# on_shore.net
KiCad netlist of a schematic drawn in EAGLE
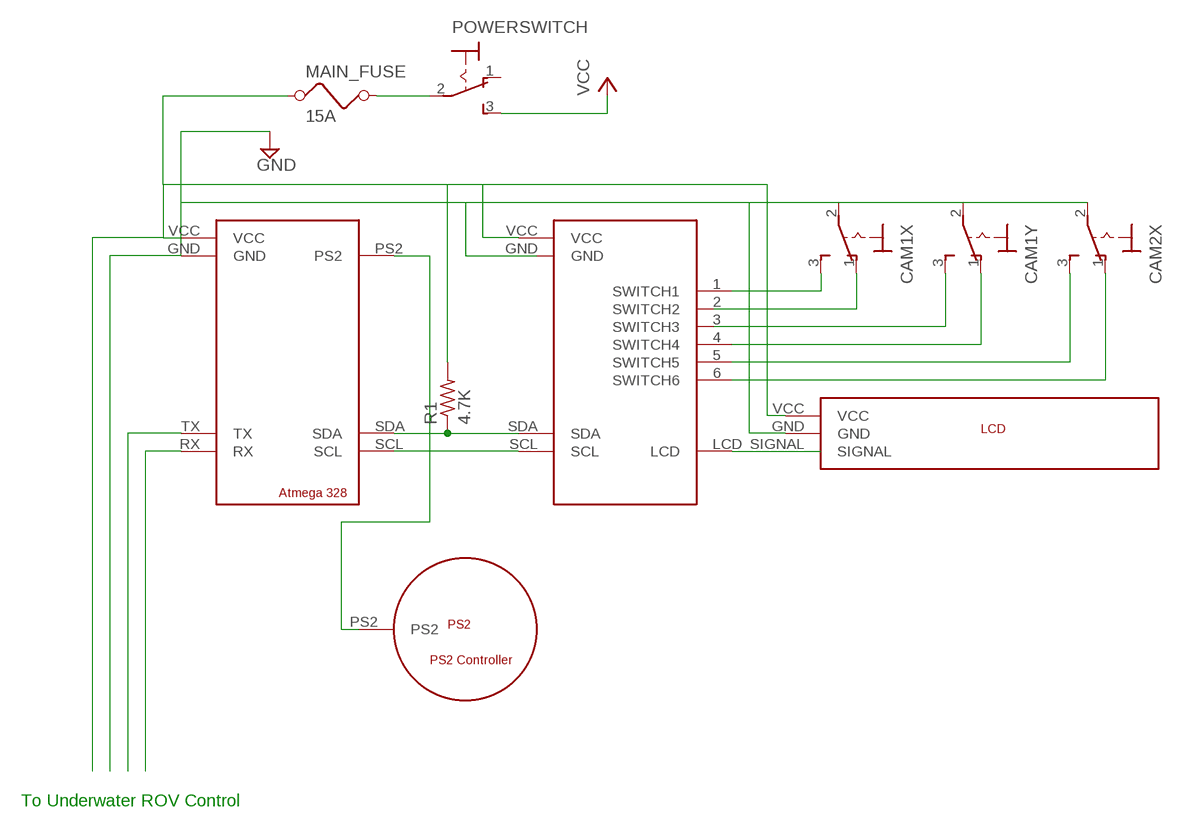
[diagram p0: schematic, sheet 1]

(export (version "E")
  (design (tool "Eeschema 10.0.6"))
  (components
    (comp (ref "CAM1X")
      (value "320-916")
      (footprint "eagle-import:320-916")
      (libsource (lib "eagle-import") (part "320-916"))
    )
    (comp (ref "CAM1Y")
      (value "320-916")
      (footprint "eagle-import:320-916")
      (libsource (lib "eagle-import") (part "320-916"))
    )
    (comp (ref "CAM2X")
      (value "320-916")
      (footprint "eagle-import:320-916")
      (libsource (lib "eagle-import") (part "320-916"))
    )
    (comp (ref "MAIN_FUSE")
      (value "15A")
      (footprint "eagle-import:FUSE")
      (libsource (lib "eagle-import") (part "FUSE"))
    )
    (comp (ref "POWERSWITCH")
      (value "320-916")
      (footprint "eagle-import:320-916")
      (libsource (lib "eagle-import") (part "320-916"))
    )
    (comp (ref "R1")
      (value "4.7K")
      (footprint "eagle-import:0204_7")
      (libsource (lib "eagle-import") (part "R-US_0204/7"))
    )
    (comp (ref "U$1")
      (value "CONTROL")
      (footprint "eagle-import:CONTROL")
      (libsource (lib "eagle-import") (part "CONTROL"))
    )
    (comp (ref "U$2")
      (value "AUX")
      (footprint "eagle-import:AUX")
      (libsource (lib "eagle-import") (part "AUX"))
    )
    (comp (ref "U$3")
      (value "LCD")
      (footprint "eagle-import:LCD")
      (libsource (lib "eagle-import") (part "LCD"))
    )
    (comp (ref "U$4")
      (value "PS2")
      (footprint "eagle-import:PS2")
      (libsource (lib "eagle-import") (part "PS2"))
    )
  )
  (nets
    (net (code "1") (name "GND") (class "Default")
      (node (ref "CAM2X") (pin "2") (pinfunction "P_2") (pintype "passive"))
      (node (ref "U$1") (pin "GND") (pinfunction "GND_GND") (pintype "bidirectional"))
      (node (ref "U$3") (pin "GND") (pinfunction "GND_GND") (pintype "bidirectional"))
    )
    (net (code "2") (name "Net-(CAM1X-S)") (class "Default")
      (node (ref "CAM1X") (pin "3") (pinfunction "S_3") (pintype "passive"))
      (node (ref "U$2") (pin "1") (pinfunction "SWITCH1_1") (pintype "bidirectional"))
    )
    (net (code "3") (name "Net-(CAM1Y-O)") (class "Default")
      (node (ref "CAM1Y") (pin "1") (pinfunction "O_1") (pintype "passive"))
      (node (ref "U$2") (pin "4") (pinfunction "SWITCH4_4") (pintype "bidirectional"))
    )
    (net (code "4") (name "Net-(CAM2X-O)") (class "Default")
      (node (ref "CAM2X") (pin "1") (pinfunction "O_1") (pintype "passive"))
      (node (ref "U$2") (pin "6") (pinfunction "SWITCH6_6") (pintype "bidirectional"))
    )
    (net (code "5") (name "Net-(CAM2X-S)") (class "Default")
      (node (ref "CAM2X") (pin "3") (pinfunction "S_3") (pintype "passive"))
      (node (ref "U$2") (pin "5") (pinfunction "SWITCH5_5") (pintype "bidirectional"))
    )
    (net (code "6") (name "Net-(MAIN_FUSE-Pad1)") (class "Default")
      (node (ref "MAIN_FUSE") (pin "1") (pinfunction "1_1") (pintype "passive"))
      (node (ref "R1") (pin "2") (pinfunction "2_2") (pintype "passive"))
      (node (ref "U$1") (pin "VCC") (pinfunction "VCC_VCC") (pintype "bidirectional"))
      (node (ref "U$2") (pin "VCC") (pinfunction "VCC_VCC") (pintype "bidirectional"))
      (node (ref "U$3") (pin "VCC") (pinfunction "VCC_VCC") (pintype "bidirectional"))
    )
    (net (code "7") (name "Net-(POWERSWITCH-P)") (class "Default")
      (node (ref "MAIN_FUSE") (pin "2") (pinfunction "2_2") (pintype "passive"))
      (node (ref "POWERSWITCH") (pin "2") (pinfunction "P_2") (pintype "passive"))
    )
    (net (code "8") (name "Net-(R1-Pad1)") (class "Default")
      (node (ref "R1") (pin "1") (pinfunction "1_1") (pintype "passive"))
      (node (ref "U$1") (pin "SDA") (pinfunction "SDA_SDA") (pintype "bidirectional"))
      (node (ref "U$2") (pin "SDA") (pinfunction "SDA_SDA") (pintype "bidirectional"))
    )
    (net (code "9") (name "Net-(U$1-PadPS2)") (class "Default")
      (node (ref "U$1") (pin "PS2") (pinfunction "PS2_PS2") (pintype "bidirectional"))
      (node (ref "U$4") (pin "PS2") (pinfunction "PS2_PS2") (pintype "bidirectional"))
    )
    (net (code "10") (name "Net-(U$1-PadSCL)") (class "Default")
      (node (ref "U$1") (pin "SCL") (pinfunction "SCL_SCL") (pintype "bidirectional"))
      (node (ref "U$2") (pin "SCL") (pinfunction "SCL_SCL") (pintype "bidirectional"))
    )
    (net (code "11") (name "VCC") (class "Default")
      (node (ref "POWERSWITCH") (pin "3") (pinfunction "S_3") (pintype "passive"))
    )
    (net (code "12") (name "unconnected-(CAM1X-O-Pad1)") (class "Default")
      (node (ref "CAM1X") (pin "1") (pinfunction "O_1") (pintype "passive"))
    )
    (net (code "13") (name "unconnected-(CAM1X-P-Pad2)") (class "Default")
      (node (ref "CAM1X") (pin "2") (pinfunction "P_2") (pintype "passive"))
    )
    (net (code "14") (name "unconnected-(CAM1Y-P-Pad2)") (class "Default")
      (node (ref "CAM1Y") (pin "2") (pinfunction "P_2") (pintype "passive"))
    )
    (net (code "15") (name "unconnected-(CAM1Y-S-Pad3)") (class "Default")
      (node (ref "CAM1Y") (pin "3") (pinfunction "S_3") (pintype "passive"))
    )
    (net (code "16") (name "unconnected-(POWERSWITCH-O-Pad1)") (class "Default")
      (node (ref "POWERSWITCH") (pin "1") (pinfunction "O_1") (pintype "passive"))
    )
    (net (code "17") (name "unconnected-(U$1-PadRX)") (class "Default")
      (node (ref "U$1") (pin "RX") (pinfunction "RX_RX") (pintype "bidirectional"))
    )
    (net (code "18") (name "unconnected-(U$1-PadTX)") (class "Default")
      (node (ref "U$1") (pin "TX") (pinfunction "TX_TX") (pintype "bidirectional"))
    )
    (net (code "19") (name "unconnected-(U$2-PadGND)") (class "Default")
      (node (ref "U$2") (pin "GND") (pinfunction "GND_GND") (pintype "bidirectional"))
    )
    (net (code "20") (name "unconnected-(U$2-PadLCD)") (class "Default")
      (node (ref "U$2") (pin "LCD") (pinfunction "LCD_LCD") (pintype "bidirectional"))
    )
    (net (code "21") (name "unconnected-(U$2-SWITCH2-Pad2)") (class "Default")
      (node (ref "U$2") (pin "2") (pinfunction "SWITCH2_2") (pintype "bidirectional"))
    )
    (net (code "22") (name "unconnected-(U$2-SWITCH3-Pad3)") (class "Default")
      (node (ref "U$2") (pin "3") (pinfunction "SWITCH3_3") (pintype "bidirectional"))
    )
    (net (code "23") (name "unconnected-(U$3-PadSIGNAL)") (class "Default")
      (node (ref "U$3") (pin "SIGNAL") (pinfunction "SIGNAL_SIGNAL") (pintype "bidirectional"))
    )
  )
)
